# MODULE_1.net
KiCad netlist of a schematic drawn in Altium Designer
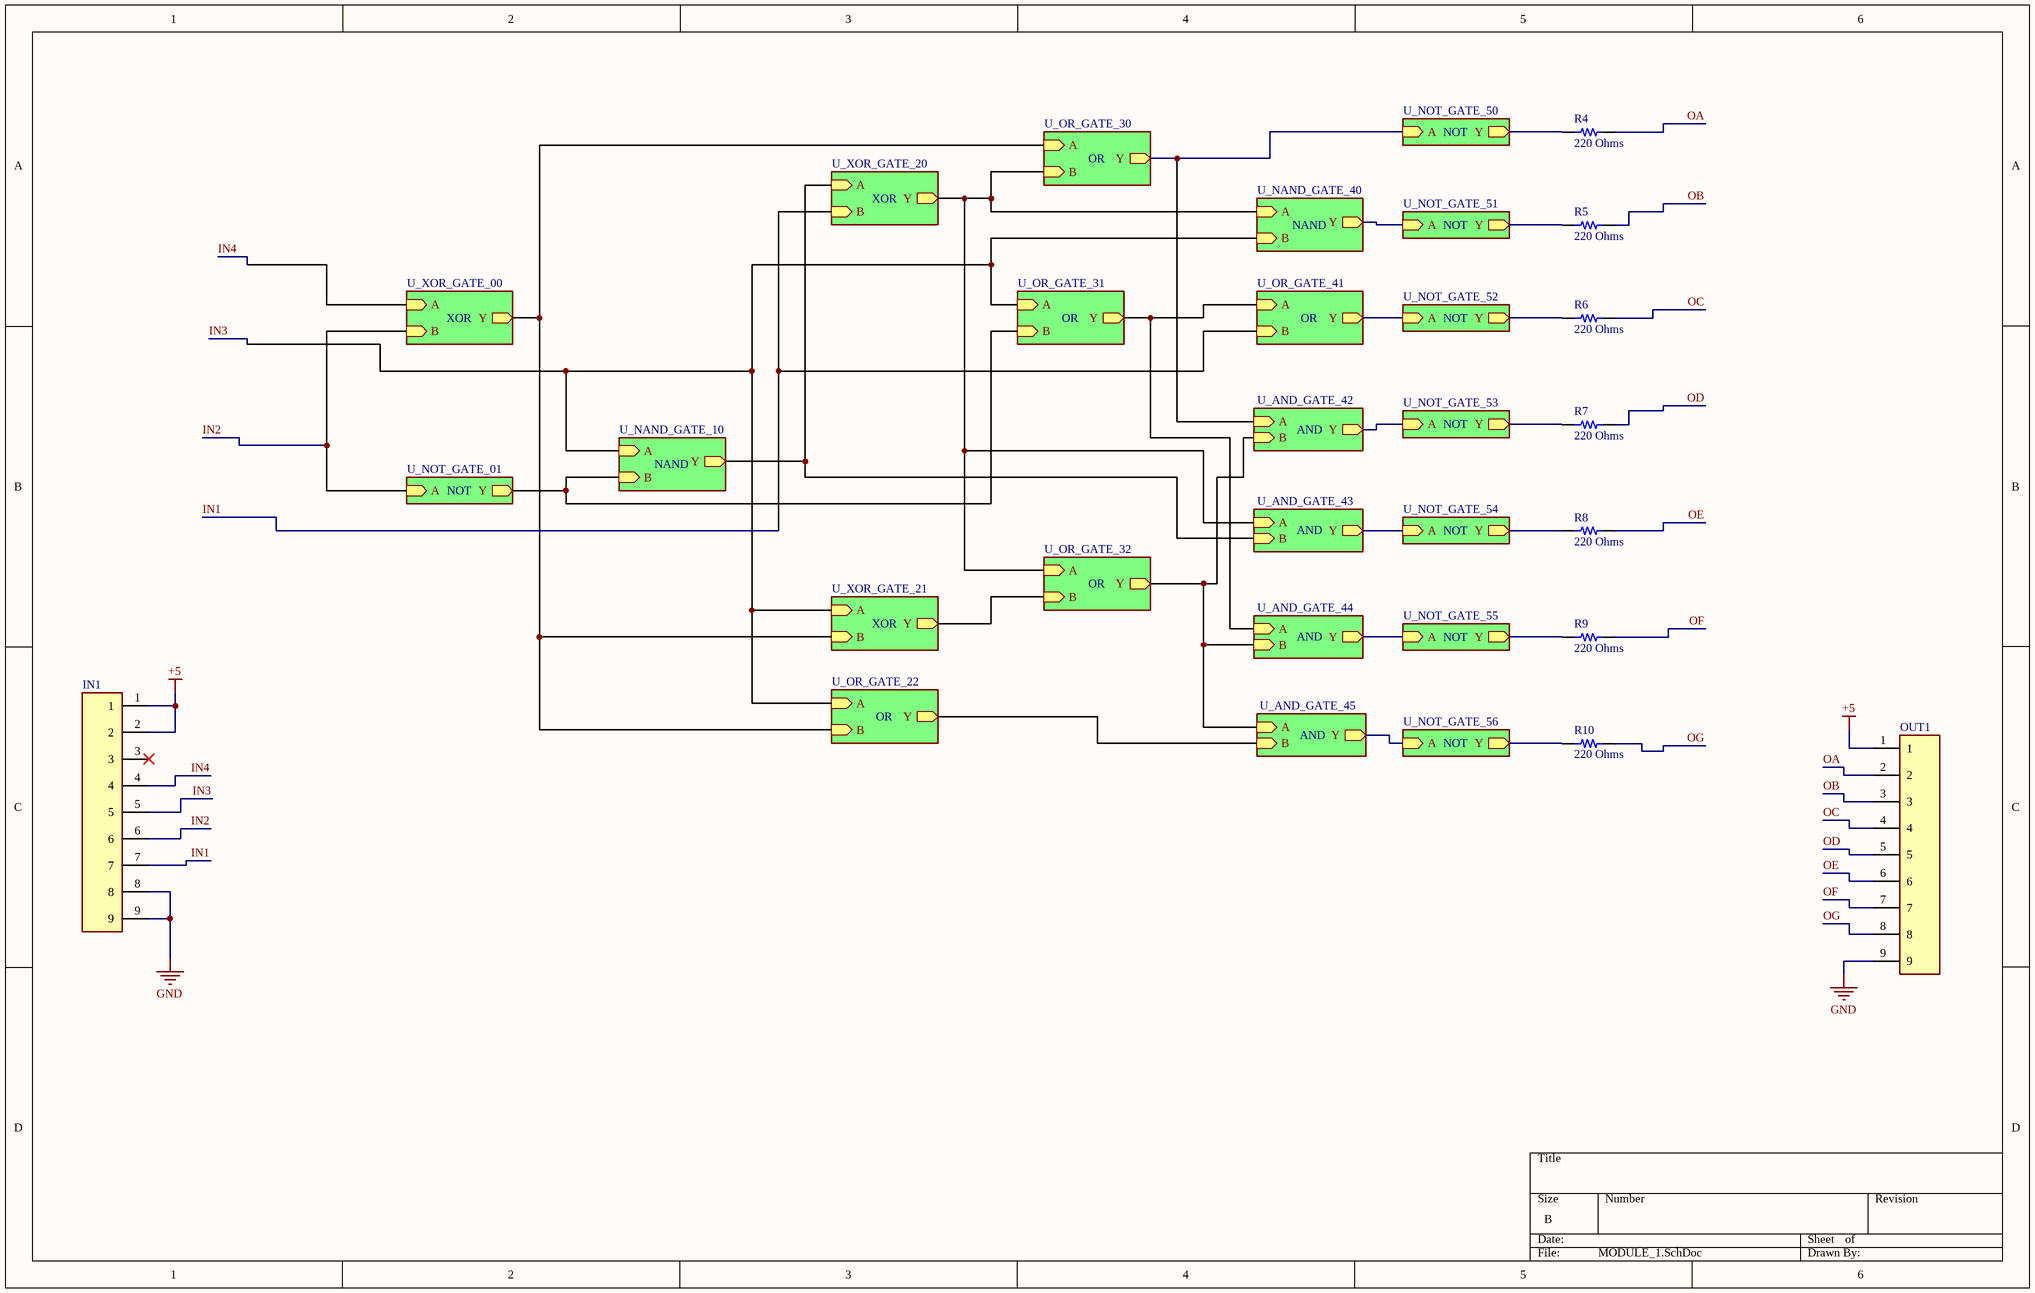
[diagram p0: MODULE_1.SchDoc]

(export (version "E")
  (design (tool "Eeschema 10.0.6"))
  (components
    (comp (ref "IN1")
      (value "2.54mm_TH_1x9_pin_header")
      (footprint "2.54mm_TH_1x9_pin_header")
      (libsource (lib "") (part "2.54mm_TH_1x9_pin_header_1"))
    )
    (comp (ref "OUT1")
      (value "2.54mm_TH_1x9_pin_header")
      (footprint "2.54mm_TH_1x9_pin_header")
      (libsource (lib "ARAF_PERSONAL_INTEGRATED_LIBRARY") (part "2.54mm_TH_1x9_pin_header"))
    )
    (comp (ref "R4")
      (value "220 Ohms")
      (footprint "RES 0603_1608")
      (description "RES SMD 220 OHM 0.5% 1/10W 0603")
      (fields
        (field (name "PART NUMBER") "ERA-3AED221V")
        (field (name "MANUFACTURER") "Panasonic Electronic Components")
      )
      (libsource (lib "Celestial Altium Library - altium_library") (part "Resistor"))
    )
    (comp (ref "R5")
      (value "220 Ohms")
      (footprint "RES 0603_1608")
      (description "RES SMD 220 OHM 0.5% 1/10W 0603")
      (fields
        (field (name "PART NUMBER") "ERA-3AED221V")
        (field (name "MANUFACTURER") "Panasonic Electronic Components")
      )
      (libsource (lib "Celestial Altium Library - altium_library") (part "Resistor"))
    )
    (comp (ref "R6")
      (value "220 Ohms")
      (footprint "RES 0603_1608")
      (description "RES SMD 220 OHM 0.5% 1/10W 0603")
      (fields
        (field (name "PART NUMBER") "ERA-3AED221V")
        (field (name "MANUFACTURER") "Panasonic Electronic Components")
      )
      (libsource (lib "Celestial Altium Library - altium_library") (part "Resistor"))
    )
    (comp (ref "R7")
      (value "220 Ohms")
      (footprint "RES 0603_1608")
      (description "RES SMD 220 OHM 0.5% 1/10W 0603")
      (fields
        (field (name "PART NUMBER") "ERA-3AED221V")
        (field (name "MANUFACTURER") "Panasonic Electronic Components")
      )
      (libsource (lib "Celestial Altium Library - altium_library") (part "Resistor"))
    )
    (comp (ref "R8")
      (value "220 Ohms")
      (footprint "RES 0603_1608")
      (description "RES SMD 220 OHM 0.5% 1/10W 0603")
      (fields
        (field (name "PART NUMBER") "ERA-3AED221V")
        (field (name "MANUFACTURER") "Panasonic Electronic Components")
      )
      (libsource (lib "Celestial Altium Library - altium_library") (part "Resistor"))
    )
    (comp (ref "R9")
      (value "220 Ohms")
      (footprint "RES 0603_1608")
      (description "RES SMD 220 OHM 0.5% 1/10W 0603")
      (fields
        (field (name "PART NUMBER") "ERA-3AED221V")
        (field (name "MANUFACTURER") "Panasonic Electronic Components")
      )
      (libsource (lib "Celestial Altium Library - altium_library") (part "Resistor"))
    )
    (comp (ref "R10")
      (value "220 Ohms")
      (footprint "RES 0603_1608")
      (description "RES SMD 220 OHM 0.5% 1/10W 0603")
      (fields
        (field (name "PART NUMBER") "ERA-3AED221V")
        (field (name "MANUFACTURER") "Panasonic Electronic Components")
      )
      (libsource (lib "Celestial Altium Library - altium_library") (part "Resistor"))
    )
  )
  (nets
    (net (code "1") (name "+5") (class "Default")
      (node (ref "IN1") (pin "1") (pinfunction "1_1") (pintype "passive"))
      (node (ref "IN1") (pin "2") (pinfunction "2_2") (pintype "passive"))
      (node (ref "OUT1") (pin "1") (pinfunction "1_1") (pintype "passive"))
    )
    (net (code "2") (name "/IN1") (class "Default")
      (node (ref "IN1") (pin "7") (pinfunction "7_7") (pintype "passive"))
    )
    (net (code "3") (name "/IN2") (class "Default")
      (node (ref "IN1") (pin "6") (pinfunction "6_6") (pintype "passive"))
    )
    (net (code "4") (name "/IN3") (class "Default")
      (node (ref "IN1") (pin "5") (pinfunction "5_5") (pintype "passive"))
    )
    (net (code "5") (name "/IN4") (class "Default")
      (node (ref "IN1") (pin "4") (pinfunction "4_4") (pintype "passive"))
    )
    (net (code "6") (name "/OA") (class "Default")
      (node (ref "OUT1") (pin "2") (pinfunction "2_2") (pintype "passive"))
      (node (ref "R4") (pin "2") (pinfunction "2_2") (pintype "passive"))
    )
    (net (code "7") (name "/OB") (class "Default")
      (node (ref "OUT1") (pin "3") (pinfunction "3_3") (pintype "passive"))
      (node (ref "R5") (pin "2") (pinfunction "2_2") (pintype "passive"))
    )
    (net (code "8") (name "/OC") (class "Default")
      (node (ref "OUT1") (pin "4") (pinfunction "4_4") (pintype "passive"))
      (node (ref "R6") (pin "2") (pinfunction "2_2") (pintype "passive"))
    )
    (net (code "9") (name "/OD") (class "Default")
      (node (ref "OUT1") (pin "5") (pinfunction "5_5") (pintype "passive"))
      (node (ref "R7") (pin "2") (pinfunction "2_2") (pintype "passive"))
    )
    (net (code "10") (name "/OE") (class "Default")
      (node (ref "OUT1") (pin "6") (pinfunction "6_6") (pintype "passive"))
      (node (ref "R8") (pin "2") (pinfunction "2_2") (pintype "passive"))
    )
    (net (code "11") (name "/OF") (class "Default")
      (node (ref "OUT1") (pin "7") (pinfunction "7_7") (pintype "passive"))
      (node (ref "R9") (pin "2") (pinfunction "2_2") (pintype "passive"))
    )
    (net (code "12") (name "/OG") (class "Default")
      (node (ref "OUT1") (pin "8") (pinfunction "8_8") (pintype "passive"))
      (node (ref "R10") (pin "2") (pinfunction "2_2") (pintype "passive"))
    )
    (net (code "13") (name "/Y") (class "Default")
      (node (ref "R10") (pin "1") (pinfunction "1_1") (pintype "passive"))
    )
    (net (code "29") (name "/Y_16") (class "Default")
      (node (ref "R8") (pin "1") (pinfunction "1_1") (pintype "passive"))
    )
    (net (code "30") (name "/Y_17") (class "Default")
      (node (ref "R4") (pin "1") (pinfunction "1_1") (pintype "passive"))
    )
    (net (code "31") (name "/Y_18") (class "Default")
      (node (ref "R5") (pin "1") (pinfunction "1_1") (pintype "passive"))
    )
    (net (code "32") (name "/Y_19") (class "Default")
      (node (ref "R6") (pin "1") (pinfunction "1_1") (pintype "passive"))
    )
    (net (code "33") (name "/Y_20") (class "Default")
      (node (ref "R7") (pin "1") (pinfunction "1_1") (pintype "passive"))
    )
    (net (code "34") (name "/Y_21") (class "Default")
      (node (ref "R9") (pin "1") (pinfunction "1_1") (pintype "passive"))
    )
    (net (code "35") (name "GND") (class "Default")
      (node (ref "IN1") (pin "8") (pinfunction "8_8") (pintype "passive"))
      (node (ref "IN1") (pin "9") (pinfunction "9_9") (pintype "passive"))
      (node (ref "OUT1") (pin "9") (pinfunction "9_9") (pintype "passive"))
    )
    (net (code "36") (name "unconnected-(IN1-Pad3)") (class "Default")
      (node (ref "IN1") (pin "3") (pinfunction "3_3") (pintype "passive+no_connect"))
    )
  )
)
